# Motor_Controller_removable_maintenance_a.net
KiCad netlist of a schematic drawn in EAGLE
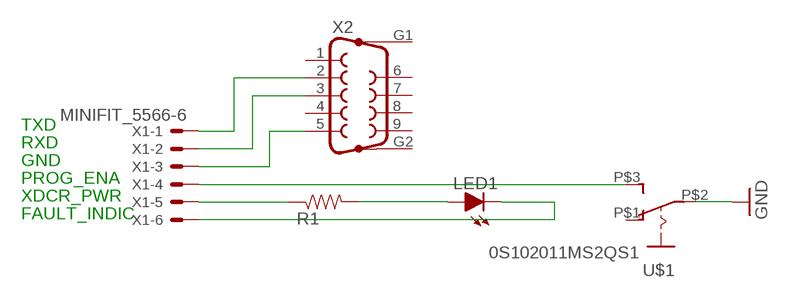
[diagram p0: schematic, sheet 1]

(export (version "E")
  (design (tool "Eeschema 10.0.6"))
  (components
    (comp (ref "LED1")
      (value "LED-0805")
      (footprint "eagle-import:LED-805")
      (libsource (lib "eagle-import") (part "LED-0805"))
    )
    (comp (ref "R1")
      (value "RESISTOR0805-RES")
      (footprint "eagle-import:0805")
      (libsource (lib "eagle-import") (part "RESISTOR0805-RES"))
    )
    (comp (ref "U$1")
      (value "0S102011MS2QS1")
      (footprint "eagle-import:0S102011MS2QS1")
      (libsource (lib "eagle-import") (part "0S102011MS2QS1"))
    )
    (comp (ref "X1")
      (value "MINIFIT_5566-6")
      (footprint "eagle-import:MINIFIT_5566-6")
      (fields (field (name "MPN") "95566-61002"))
      (libsource (lib "eagle-import") (part "MINIFIT_5566-6"))
    )
    (comp (ref "X2")
      (value "F09HP")
      (footprint "eagle-import:F09HP")
      (libsource (lib "eagle-import") (part "F09HP"))
    )
  )
  (nets
    (net (code "1") (name "GND") (class "Default")
      (node (ref "U$1") (pin "P$2") (pinfunction "P_P$2") (pintype "passive"))
    )
    (net (code "2") (name "Net-(LED1-PadA)") (class "Default")
      (node (ref "LED1") (pin "A") (pinfunction "A_A") (pintype "passive"))
      (node (ref "R1") (pin "2") (pinfunction "2_2") (pintype "passive"))
    )
    (net (code "3") (name "Net-(U$1-S)") (class "Default")
      (node (ref "U$1") (pin "P$3") (pinfunction "S_P$3") (pintype "passive"))
      (node (ref "X1") (pin "4") (pinfunction "S_4") (pintype "passive"))
    )
    (net (code "4") (name "Net-(X1A-S)") (class "Default")
      (node (ref "X1") (pin "1") (pinfunction "S_1") (pintype "passive"))
      (node (ref "X2") (pin "2") (pinfunction "2_2") (pintype "passive"))
    )
    (net (code "5") (name "Net-(X1B-S)") (class "Default")
      (node (ref "X1") (pin "2") (pinfunction "S_2") (pintype "passive"))
      (node (ref "X2") (pin "3") (pinfunction "3_3") (pintype "passive"))
    )
    (net (code "6") (name "Net-(X1C-S)") (class "Default")
      (node (ref "X1") (pin "3") (pinfunction "S_3") (pintype "passive"))
      (node (ref "X2") (pin "5") (pinfunction "5_5") (pintype "passive"))
    )
    (net (code "7") (name "Net-(X1E-S)") (class "Default")
      (node (ref "R1") (pin "1") (pinfunction "1_1") (pintype "passive"))
      (node (ref "X1") (pin "5") (pinfunction "S_5") (pintype "passive"))
    )
    (net (code "8") (name "Net-(X1F-S)") (class "Default")
      (node (ref "LED1") (pin "C") (pinfunction "C_C") (pintype "passive"))
      (node (ref "X1") (pin "6") (pinfunction "S_6") (pintype "passive"))
    )
    (net (code "9") (name "unconnected-(U$1-O-PadP$1)") (class "Default")
      (node (ref "U$1") (pin "P$1") (pinfunction "O_P$1") (pintype "passive"))
    )
    (net (code "10") (name "unconnected-(X2-Pad1)") (class "Default")
      (node (ref "X2") (pin "1") (pinfunction "1_1") (pintype "passive"))
    )
    (net (code "11") (name "unconnected-(X2-Pad4)") (class "Default")
      (node (ref "X2") (pin "4") (pinfunction "4_4") (pintype "passive"))
    )
    (net (code "12") (name "unconnected-(X2-Pad6)") (class "Default")
      (node (ref "X2") (pin "6") (pinfunction "6_6") (pintype "passive"))
    )
    (net (code "13") (name "unconnected-(X2-Pad7)") (class "Default")
      (node (ref "X2") (pin "7") (pinfunction "7_7") (pintype "passive"))
    )
    (net (code "14") (name "unconnected-(X2-Pad8)") (class "Default")
      (node (ref "X2") (pin "8") (pinfunction "8_8") (pintype "passive"))
    )
    (net (code "15") (name "unconnected-(X2-Pad9)") (class "Default")
      (node (ref "X2") (pin "9") (pinfunction "9_9") (pintype "passive"))
    )
    (net (code "16") (name "unconnected-(X2-PadG1)") (class "Default")
      (node (ref "X2") (pin "G1") (pinfunction "G1_G1") (pintype "passive"))
    )
    (net (code "17") (name "unconnected-(X2-PadG2)") (class "Default")
      (node (ref "X2") (pin "G2") (pinfunction "G2_G2") (pintype "passive"))
    )
  )
)
